# dualstepper.net
KiCad netlist of a schematic drawn in EAGLE
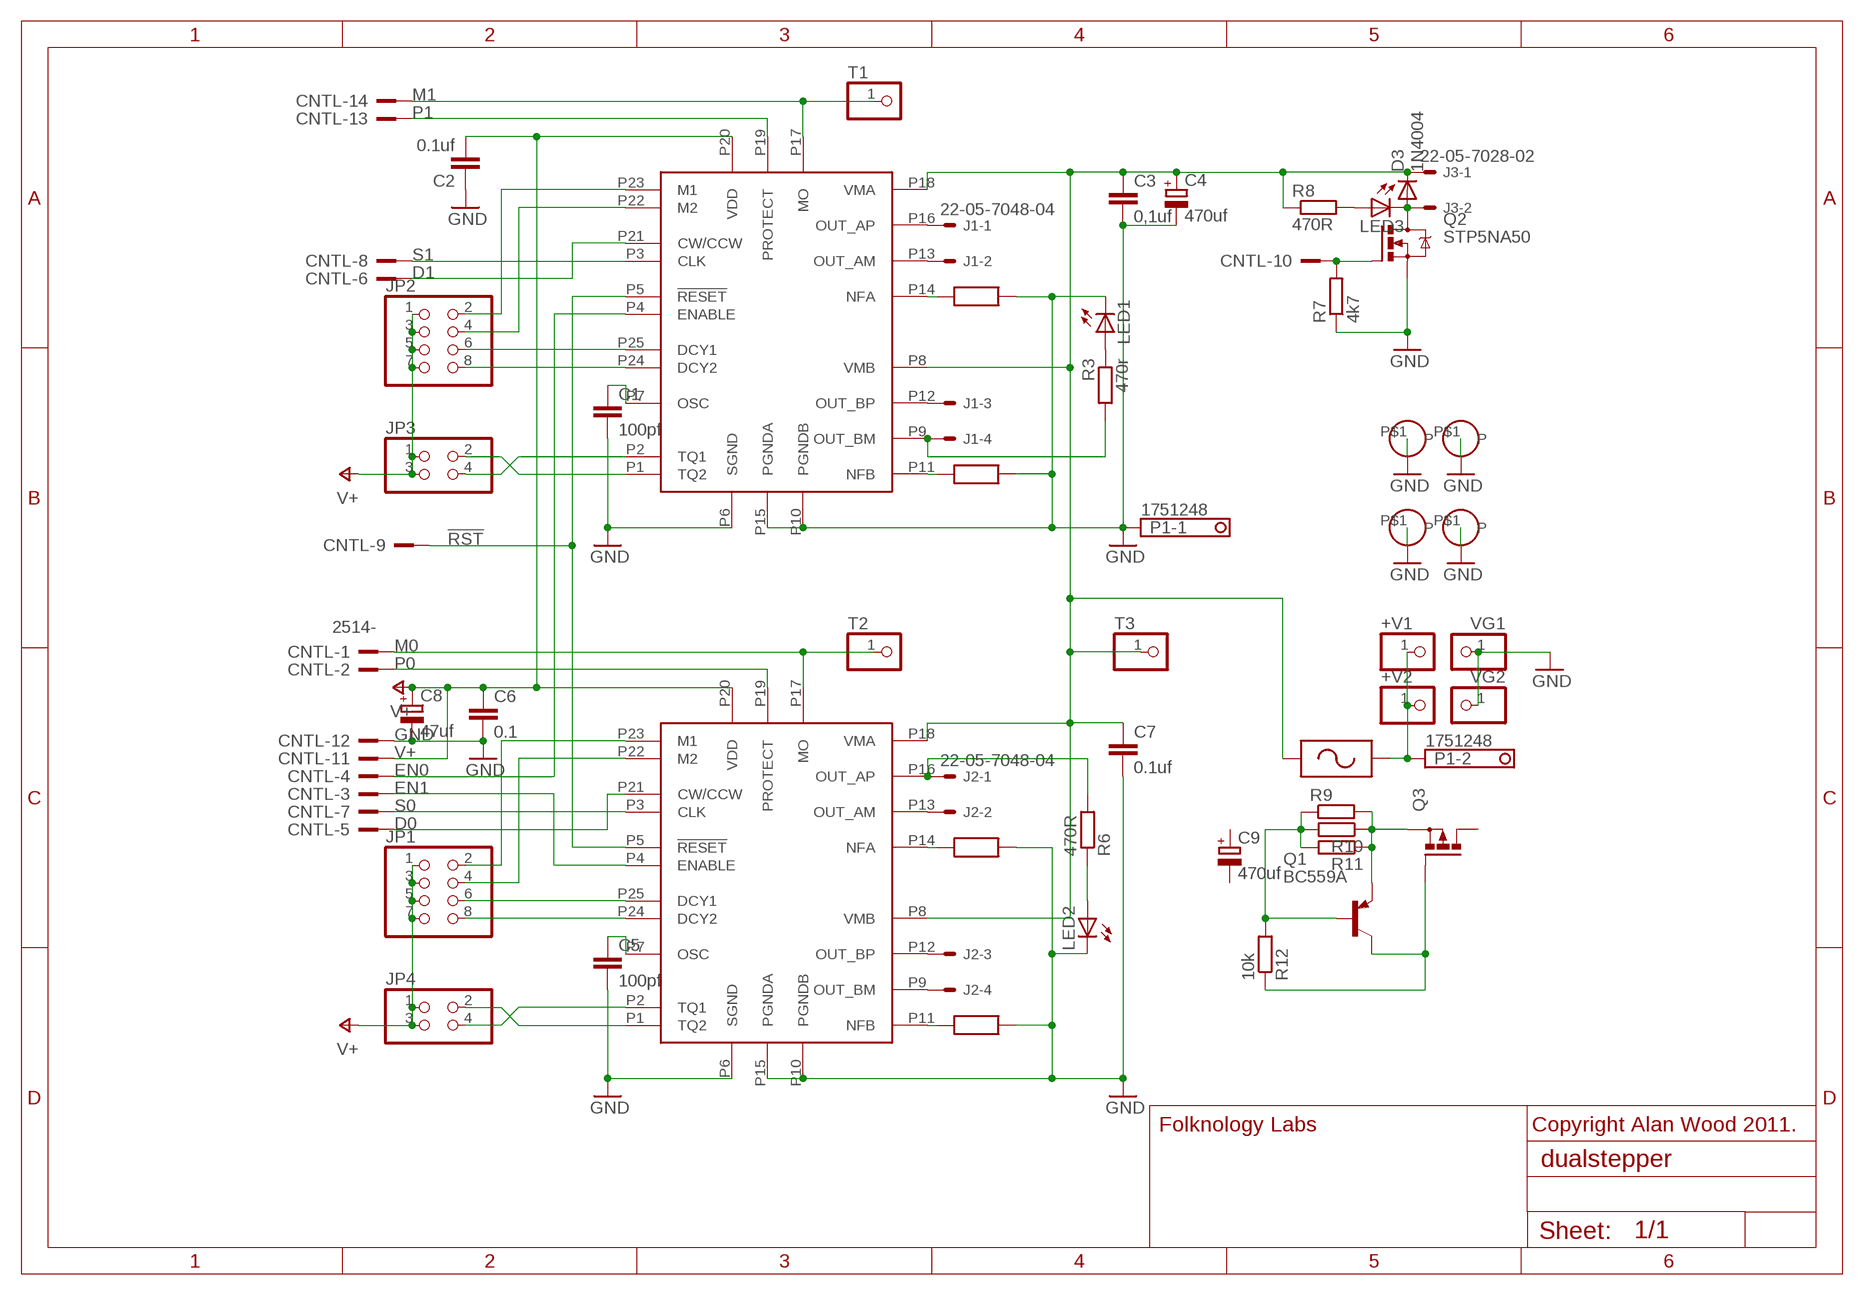
[diagram p0: schematic, sheet 1]

(export (version "E")
  (design (tool "Eeschema 10.0.6"))
  (components
    (comp (ref "+V1")
      (value "PINHD-1X1")
      (footprint "eagle-import:1X01")
      (fields (field (name "MF") "MOLEX") (field (name "MPN") "90120-0761"))
      (libsource (lib "eagle-import") (part "PINHD-1X1"))
    )
    (comp (ref "+V2")
      (value "PINHD-1X1")
      (footprint "eagle-import:1X01")
      (fields (field (name "MF") "MOLEX") (field (name "MPN") "90120-0761"))
      (libsource (lib "eagle-import") (part "PINHD-1X1"))
    )
    (comp (ref "C1")
      (value "100pf")
      (footprint "eagle-import:C025-024X044")
      (fields (field (name "MF") "AVX") (field (name "MPN") "SR151A101JAR"))
      (libsource (lib "eagle-import") (part "C-EU025-024X044"))
    )
    (comp (ref "C2")
      (value "0.1uf")
      (footprint "eagle-import:C025-024X044")
      (fields (field (name "MF") "VISHAY") (field (name "MPN") "K104K15X7RF53L2"))
      (libsource (lib "eagle-import") (part "C-EU025-024X044"))
    )
    (comp (ref "C3")
      (value "0,1uf")
      (footprint "eagle-import:C025-024X044")
      (fields (field (name "MF") "VISHAY") (field (name "MPN") "K104K15X7RF53L2"))
      (libsource (lib "eagle-import") (part "C-EU025-024X044"))
    )
    (comp (ref "C4")
      (value "470uf")
      (footprint "eagle-import:E22-9")
      (fields (field (name "MF") "MULTICOMP") (field (name "MPN") "MCTEA471M1EB-1021P"))
      (libsource (lib "eagle-import") (part "CPOL-EUE22-9AXIAL"))
    )
    (comp (ref "C5")
      (value "100pf")
      (footprint "eagle-import:C025-024X044")
      (fields (field (name "MF") "AVX") (field (name "MPN") "SR151A101JAR"))
      (libsource (lib "eagle-import") (part "C-EU025-024X044"))
    )
    (comp (ref "C6")
      (value "0.1")
      (footprint "eagle-import:C025-024X044")
      (fields (field (name "MF") "VISHAY") (field (name "MPN") "K104K15X7RF53L2"))
      (libsource (lib "eagle-import") (part "C-EU025-024X044"))
    )
    (comp (ref "C7")
      (value "0.1uf")
      (footprint "eagle-import:C025-024X044")
      (fields (field (name "MF") "VISHAY") (field (name "MPN") "K104K15X7RF53L2"))
      (libsource (lib "eagle-import") (part "C-EU025-024X044"))
    )
    (comp (ref "C8")
      (value "47uf")
      (footprint "eagle-import:E1,8-4")
      (fields (field (name "MF") "RUBYCON") (field (name "MPN") "16YXF47MEFC5X11"))
      (libsource (lib "eagle-import") (part "CPOL-EUE1.8-4"))
    )
    (comp (ref "C9")
      (value "470uf")
      (footprint "eagle-import:E3,5-8")
      (fields (field (name "MF") "MULTICOMP") (field (name "MPN") "MCTEA471M1EB-1021P"))
      (libsource (lib "eagle-import") (part "CPOL-EUE3.5-8"))
    )
    (comp (ref "CNTL")
      (value "2514-")
      (footprint "eagle-import:PAK100_2500-14")
      (fields
        (field (name "MF") "HARTING")
        (field (name "MPN") "09 18 510 7323")
        (field (name "OC_FARNELL") "1096980")
      )
      (libsource (lib "eagle-import") (part "2514-"))
    )
    (comp (ref "D3")
      (value "1N4004")
      (footprint "eagle-import:D-7.5")
      (fields (field (name "MF") "ON SEMICONDUCTOR") (field (name "MPN") "1N4004RL"))
      (libsource (lib "eagle-import") (part "DIODE-D-7.5"))
    )
    (comp (ref "J1")
      (value "22-05-7048-04")
      (footprint "eagle-import:7395-04")
      (fields
        (field (name "MF") "MOLEX")
        (field (name "MPN") "22-05-7048")
        (field (name "OC_FARNELL") "9731628")
      )
      (libsource (lib "eagle-import") (part "22-?-0405-7048"))
    )
    (comp (ref "J2")
      (value "22-05-7048-04")
      (footprint "eagle-import:7395-04")
      (fields
        (field (name "MF") "MOLEX")
        (field (name "MPN") "22-05-7048")
        (field (name "OC_FARNELL") "9731628")
      )
      (libsource (lib "eagle-import") (part "22-?-0405-7048"))
    )
    (comp (ref "J3")
      (value "22-05-7028-02")
      (footprint "eagle-import:7395-02")
      (fields
        (field (name "MF") "MOLEX")
        (field (name "MPN") "22-05-7028")
        (field (name "OC_FARNELL") "9731601")
      )
      (libsource (lib "eagle-import") (part "22-?-0205-7028"))
    )
    (comp (ref "JP1")
      (value "PINHD-2X4")
      (footprint "eagle-import:2X04")
      (fields (field (name "MF") "HARWIN") (field (name "MPN") "M20-9980446"))
      (libsource (lib "eagle-import") (part "PINHD-2X4"))
    )
    (comp (ref "JP2")
      (value "PINHD-2X4")
      (footprint "eagle-import:2X04")
      (fields (field (name "MF") "HARWIN") (field (name "MPN") "M20-9980446"))
      (libsource (lib "eagle-import") (part "PINHD-2X4"))
    )
    (comp (ref "JP3")
      (value "PINHD-2X2")
      (footprint "eagle-import:2X02")
      (fields (field (name "MF") "SAMTEC") (field (name "MPN") "TSW-101-07-T-D"))
      (libsource (lib "eagle-import") (part "PINHD-2X2"))
    )
    (comp (ref "JP4")
      (value "PINHD-2X2")
      (footprint "eagle-import:2X02")
      (fields (field (name "MF") "SAMTEC") (field (name "MPN") "TSW-101-07-T-D"))
      (libsource (lib "eagle-import") (part "PINHD-2X2"))
    )
    (comp (ref "LED1")
      (value "LED3MM")
      (footprint "eagle-import:LED3MM")
      (fields (field (name "MF") "KINGBRIGHT") (field (name "MPN") "L-93WEYW"))
      (libsource (lib "eagle-import") (part "LED3MM"))
    )
    (comp (ref "LED2")
      (value "LED3MM")
      (footprint "eagle-import:LED3MM")
      (fields (field (name "MF") "KINGBRIGHT") (field (name "MPN") "L-93WEYW"))
      (libsource (lib "eagle-import") (part "LED3MM"))
    )
    (comp (ref "LED3")
      (value "LED3MM")
      (footprint "eagle-import:LED3MM")
      (fields (field (name "MF") "KINGBRIGHT") (field (name "MPN") "L-93WEYW"))
      (libsource (lib "eagle-import") (part "LED3MM"))
    )
    (comp (ref "P1")
      (value "1751248")
      (footprint "eagle-import:1751248")
      (fields
        (field (name "MF") "CAMDEN")
        (field (name "MPN") "CTB3051/2")
        (field (name "OC_FARNELL") "3882615")
      )
      (libsource (lib "eagle-import") (part "1751248"))
    )
    (comp (ref "Q1")
      (value "BC559A")
      (footprint "eagle-import:TO92-EBC")
      (libsource (lib "eagle-import") (part "BC559A"))
    )
    (comp (ref "Q2")
      (value "STP5NA50")
      (footprint "eagle-import:TO220BV")
      (fields (field (name "MF") "STMICROELECTRONICS") (field (name "MPN") "STP55NF06L."))
      (libsource (lib "eagle-import") (part "STP5NA50"))
    )
    (comp (ref "Q3")
      (value "PMOSFET_PTO220BV")
      (footprint "eagle-import:TO220BV")
      (libsource (lib "eagle-import") (part "PMOSFET_PTO220BV"))
    )
    (comp (ref "R1")
      (value "R22")
      (footprint "eagle-import:R20")
      (fields (field (name "MF") "WELWYN") (field (name "MPN") "WP4S-R22JA2"))
      (libsource (lib "eagle-import") (part "3W-WIREWOUND-RESISTOR"))
    )
    (comp (ref "R2")
      (value "R22")
      (footprint "eagle-import:R20")
      (fields (field (name "MF") "WELWYN") (field (name "MPN") "WP4S-R22JA2"))
      (libsource (lib "eagle-import") (part "3W-WIREWOUND-RESISTOR"))
    )
    (comp (ref "R3")
      (value "470r")
      (footprint "eagle-import:0204_7")
      (fields (field (name "MF") "WELWYN") (field (name "MPN") "MFR4 470R 1%"))
      (libsource (lib "eagle-import") (part "R-EU_0204/7"))
    )
    (comp (ref "R4")
      (value "R22")
      (footprint "eagle-import:R20")
      (fields (field (name "MF") "WELWYN") (field (name "MPN") "WP4S-R22JA2"))
      (libsource (lib "eagle-import") (part "3W-WIREWOUND-RESISTOR"))
    )
    (comp (ref "R5")
      (value "R22")
      (footprint "eagle-import:R20")
      (fields (field (name "MF") "WELWYN") (field (name "MPN") "WP4S-R22JA2"))
      (libsource (lib "eagle-import") (part "3W-WIREWOUND-RESISTOR"))
    )
    (comp (ref "R6")
      (value "470R")
      (footprint "eagle-import:0204_7")
      (fields (field (name "MF") "WELWYN") (field (name "MPN") "MFR4 470R 1%"))
      (libsource (lib "eagle-import") (part "R-EU_0204/7"))
    )
    (comp (ref "R7")
      (value "4k7")
      (footprint "eagle-import:0204_7")
      (fields (field (name "MF") "WELWYN") (field (name "MPN") "MFR4 10K 1%"))
      (libsource (lib "eagle-import") (part "resistor_R-EU_0204/7"))
    )
    (comp (ref "R8")
      (value "470R")
      (footprint "eagle-import:0204_7")
      (fields (field (name "MF") "WELWYN") (field (name "MPN") "MFR4 470R 1%"))
      (libsource (lib "eagle-import") (part "resistor_R-EU_0204/7"))
    )
    (comp (ref "R9")
      (value "R-EU_0411/3V")
      (footprint "eagle-import:0411V")
      (libsource (lib "eagle-import") (part "resistor_R-EU_0411/3V"))
    )
    (comp (ref "R10")
      (value "R-EU_0411/3V")
      (footprint "eagle-import:0411V")
      (libsource (lib "eagle-import") (part "resistor_R-EU_0411/3V"))
    )
    (comp (ref "R11")
      (value "R-EU_0411/3V")
      (footprint "eagle-import:0411V")
      (libsource (lib "eagle-import") (part "resistor_R-EU_0411/3V"))
    )
    (comp (ref "R12")
      (value "10k")
      (footprint "eagle-import:0204_7")
      (fields (field (name "MF") "WELWYN") (field (name "MPN") "MFR4 470R 1%"))
      (libsource (lib "eagle-import") (part "R-EU_0204/7"))
    )
    (comp (ref "T1")
      (value "PINHD-1X1")
      (footprint "eagle-import:1X01")
      (fields (field (name "MF") "MOLEX") (field (name "MPN") "90120-0761"))
      (libsource (lib "eagle-import") (part "PINHD-1X1"))
    )
    (comp (ref "T2")
      (value "PINHD-1X1")
      (footprint "eagle-import:1X01")
      (fields (field (name "MF") "MOLEX") (field (name "MPN") "90120-0761"))
      (libsource (lib "eagle-import") (part "PINHD-1X1"))
    )
    (comp (ref "T3")
      (value "PINHD-1X1")
      (footprint "eagle-import:1X01")
      (fields (field (name "MF") "MOLEX") (field (name "MPN") "90120-0761"))
      (libsource (lib "eagle-import") (part "PINHD-1X1"))
    )
    (comp (ref "U$1")
      (value "TB6560AHQ")
      (footprint "eagle-import:HZIP25-P-1.27")
      (libsource (lib "eagle-import") (part "TB6560AHQ"))
    )
    (comp (ref "U$2")
      (value "TB6560AHQ")
      (footprint "eagle-import:HZIP25-P-1.27")
      (libsource (lib "eagle-import") (part "TB6560AHQ"))
    )
    (comp (ref "U$3")
      (value "HOLE")
      (footprint "eagle-import:HOLE")
      (libsource (lib "eagle-import") (part "HOLE"))
    )
    (comp (ref "U$4")
      (value "HOLE")
      (footprint "eagle-import:HOLE")
      (libsource (lib "eagle-import") (part "HOLE"))
    )
    (comp (ref "U$5")
      (value "HOLE")
      (footprint "eagle-import:HOLE")
      (libsource (lib "eagle-import") (part "HOLE"))
    )
    (comp (ref "U$6")
      (value "HOLE")
      (footprint "eagle-import:HOLE")
      (libsource (lib "eagle-import") (part "HOLE"))
    )
    (comp (ref "U$7")
      (value "RXEFXXX-RAYCHEM-POLYSWITCH10.2")
      (footprint "eagle-import:2_10.2")
      (fields (field (name "MF") "TE CONNECTIVITY / RAYCHEM") (field (name "MPN") "AGRF1000"))
      (libsource (lib "eagle-import") (part "RXEFXXX-RAYCHEM-POLYSWITCH10.2"))
    )
    (comp (ref "VG1")
      (value "PINHD-1X1")
      (footprint "eagle-import:1X01")
      (fields (field (name "MF") "MOLEX") (field (name "MPN") "90120-0761"))
      (libsource (lib "eagle-import") (part "PINHD-1X1"))
    )
    (comp (ref "VG2")
      (value "PINHD-1X1")
      (footprint "eagle-import:1X01")
      (fields (field (name "MF") "MOLEX") (field (name "MPN") "90120-0761"))
      (libsource (lib "eagle-import") (part "PINHD-1X1"))
    )
  )
  (nets
    (net (code "1") (name "/D0") (class "Default")
      (node (ref "CNTL") (pin "5") (pinfunction "KL_5") (pintype "passive"))
      (node (ref "U$1") (pin "P21") (pinfunction "CW/CCW_P21") (pintype "input"))
    )
    (net (code "2") (name "/D1") (class "Default")
      (node (ref "CNTL") (pin "6") (pinfunction "KL_6") (pintype "passive"))
      (node (ref "U$2") (pin "P21") (pinfunction "CW/CCW_P21") (pintype "input"))
    )
    (net (code "3") (name "/EN0") (class "Default")
      (node (ref "CNTL") (pin "4") (pinfunction "KL_4") (pintype "passive"))
      (node (ref "U$2") (pin "P4") (pinfunction "ENABLE_P4") (pintype "input"))
    )
    (net (code "4") (name "/EN1") (class "Default")
      (node (ref "CNTL") (pin "3") (pinfunction "KL_3") (pintype "passive"))
      (node (ref "U$1") (pin "P4") (pinfunction "ENABLE_P4") (pintype "input"))
    )
    (net (code "5") (name "/M0") (class "Default")
      (node (ref "CNTL") (pin "1") (pinfunction "KL_1") (pintype "passive"))
      (node (ref "T2") (pin "1") (pinfunction "1_1") (pintype "passive"))
      (node (ref "U$1") (pin "P17") (pinfunction "MO_P17") (pintype "output"))
    )
    (net (code "6") (name "/M1") (class "Default")
      (node (ref "CNTL") (pin "14") (pinfunction "KL_14") (pintype "passive"))
      (node (ref "T1") (pin "1") (pinfunction "1_1") (pintype "passive"))
      (node (ref "U$2") (pin "P17") (pinfunction "MO_P17") (pintype "output"))
    )
    (net (code "7") (name "/P0") (class "Default")
      (node (ref "CNTL") (pin "2") (pinfunction "KL_2") (pintype "passive"))
      (node (ref "U$1") (pin "P19") (pinfunction "PROTECT_P19") (pintype "output"))
    )
    (net (code "8") (name "/P1") (class "Default")
      (node (ref "CNTL") (pin "13") (pinfunction "KL_13") (pintype "passive"))
      (node (ref "U$2") (pin "P19") (pinfunction "PROTECT_P19") (pintype "output"))
    )
    (net (code "9") (name "/S0") (class "Default")
      (node (ref "CNTL") (pin "7") (pinfunction "KL_7") (pintype "passive"))
      (node (ref "U$1") (pin "P3") (pinfunction "CLK_P3") (pintype "input"))
    )
    (net (code "10") (name "/S1") (class "Default")
      (node (ref "CNTL") (pin "8") (pinfunction "KL_8") (pintype "passive"))
      (node (ref "U$2") (pin "P3") (pinfunction "CLK_P3") (pintype "input"))
    )
    (net (code "11") (name "/~{RST}") (class "Default")
      (node (ref "CNTL") (pin "9") (pinfunction "KL_9") (pintype "passive"))
      (node (ref "U$1") (pin "P5") (pinfunction "~{RESET}_P5") (pintype "bidirectional"))
      (node (ref "U$2") (pin "P5") (pinfunction "~{RESET}_P5") (pintype "bidirectional"))
    )
    (net (code "12") (name "GND") (class "Default")
      (node (ref "C1") (pin "2") (pinfunction "2_2") (pintype "passive"))
      (node (ref "C2") (pin "1") (pinfunction "1_1") (pintype "passive"))
      (node (ref "C3") (pin "2") (pinfunction "2_2") (pintype "passive"))
      (node (ref "C4") (pin "-") (pinfunction "-_-") (pintype "passive"))
      (node (ref "C5") (pin "2") (pinfunction "2_2") (pintype "passive"))
      (node (ref "C6") (pin "2") (pinfunction "2_2") (pintype "passive"))
      (node (ref "C7") (pin "2") (pinfunction "2_2") (pintype "passive"))
      (node (ref "C8") (pin "-") (pinfunction "-_-") (pintype "passive"))
      (node (ref "CNTL") (pin "12") (pinfunction "KL_12") (pintype "passive"))
      (node (ref "LED1") (pin "K") (pinfunction "C_K") (pintype "passive"))
      (node (ref "LED2") (pin "K") (pinfunction "C_K") (pintype "passive"))
      (node (ref "P1") (pin "1") (pinfunction "K_1") (pintype "passive"))
      (node (ref "Q2") (pin "S") (pinfunction "S_S") (pintype "passive"))
      (node (ref "R1") (pin "P$2") (pinfunction "2_P$2") (pintype "passive"))
      (node (ref "R2") (pin "P$2") (pinfunction "2_P$2") (pintype "passive"))
      (node (ref "R4") (pin "P$2") (pinfunction "2_P$2") (pintype "passive"))
      (node (ref "R5") (pin "P$2") (pinfunction "2_P$2") (pintype "passive"))
      (node (ref "R7") (pin "1") (pinfunction "1_1") (pintype "passive"))
      (node (ref "U$1") (pin "P10") (pinfunction "PGNDB_P10") (pintype "bidirectional"))
      (node (ref "U$1") (pin "P15") (pinfunction "PGNDA_P15") (pintype "bidirectional"))
      (node (ref "U$1") (pin "P6") (pinfunction "SGND_P6") (pintype "power_in"))
      (node (ref "U$2") (pin "P10") (pinfunction "PGNDB_P10") (pintype "bidirectional"))
      (node (ref "U$2") (pin "P15") (pinfunction "PGNDA_P15") (pintype "bidirectional"))
      (node (ref "U$2") (pin "P6") (pinfunction "SGND_P6") (pintype "power_in"))
      (node (ref "U$3") (pin "P$1") (pinfunction "P_P$1") (pintype "bidirectional"))
      (node (ref "U$4") (pin "P$1") (pinfunction "P_P$1") (pintype "bidirectional"))
      (node (ref "U$5") (pin "P$1") (pinfunction "P_P$1") (pintype "bidirectional"))
      (node (ref "U$6") (pin "P$1") (pinfunction "P_P$1") (pintype "bidirectional"))
      (node (ref "VG1") (pin "1") (pinfunction "1_1") (pintype "passive"))
      (node (ref "VG2") (pin "1") (pinfunction "1_1") (pintype "passive"))
    )
    (net (code "13") (name "Net-(CNTLB-KL)") (class "Default")
      (node (ref "CNTL") (pin "10") (pinfunction "KL_10") (pintype "passive"))
      (node (ref "Q2") (pin "G") (pinfunction "G_G") (pintype "passive"))
      (node (ref "R7") (pin "2") (pinfunction "2_2") (pintype "passive"))
    )
    (net (code "14") (name "Net-(J1A-S)") (class "Default")
      (node (ref "J1") (pin "1") (pinfunction "S_1") (pintype "passive"))
      (node (ref "U$2") (pin "P16") (pinfunction "OUT_AP_P16") (pintype "output"))
    )
    (net (code "15") (name "Net-(J1B-S)") (class "Default")
      (node (ref "J1") (pin "2") (pinfunction "S_2") (pintype "passive"))
      (node (ref "U$2") (pin "P13") (pinfunction "OUT_AM_P13") (pintype "output"))
    )
    (net (code "16") (name "Net-(J1C-S)") (class "Default")
      (node (ref "J1") (pin "3") (pinfunction "S_3") (pintype "passive"))
      (node (ref "U$2") (pin "P12") (pinfunction "OUT_BP_P12") (pintype "output"))
    )
    (net (code "17") (name "Net-(J1D-S)") (class "Default")
      (node (ref "J1") (pin "4") (pinfunction "S_4") (pintype "passive"))
      (node (ref "R3") (pin "2") (pinfunction "2_2") (pintype "passive"))
      (node (ref "U$2") (pin "P9") (pinfunction "OUT_BM_P9") (pintype "output"))
    )
    (net (code "18") (name "Net-(J2A-S)") (class "Default")
      (node (ref "J2") (pin "1") (pinfunction "S_1") (pintype "passive"))
      (node (ref "R6") (pin "2") (pinfunction "2_2") (pintype "passive"))
      (node (ref "U$1") (pin "P16") (pinfunction "OUT_AP_P16") (pintype "output"))
    )
    (net (code "19") (name "Net-(J2B-S)") (class "Default")
      (node (ref "J2") (pin "2") (pinfunction "S_2") (pintype "passive"))
      (node (ref "U$1") (pin "P13") (pinfunction "OUT_AM_P13") (pintype "output"))
    )
    (net (code "20") (name "Net-(J2C-S)") (class "Default")
      (node (ref "J2") (pin "3") (pinfunction "S_3") (pintype "passive"))
      (node (ref "U$1") (pin "P12") (pinfunction "OUT_BP_P12") (pintype "output"))
    )
    (net (code "21") (name "Net-(J2D-S)") (class "Default")
      (node (ref "J2") (pin "4") (pinfunction "S_4") (pintype "passive"))
      (node (ref "U$1") (pin "P9") (pinfunction "OUT_BM_P9") (pintype "output"))
    )
    (net (code "22") (name "Net-(J3A-S)") (class "Default")
      (node (ref "C3") (pin "1") (pinfunction "1_1") (pintype "passive"))
      (node (ref "C4") (pin "+") (pinfunction "+_+") (pintype "passive"))
      (node (ref "C7") (pin "1") (pinfunction "1_1") (pintype "passive"))
      (node (ref "D3") (pin "C") (pinfunction "C_C") (pintype "passive"))
      (node (ref "J3") (pin "1") (pinfunction "S_1") (pintype "passive"))
      (node (ref "R8") (pin "1") (pinfunction "1_1") (pintype "passive"))
      (node (ref "T3") (pin "1") (pinfunction "1_1") (pintype "passive"))
      (node (ref "U$1") (pin "P18") (pinfunction "VMA_P18") (pintype "power_in"))
      (node (ref "U$1") (pin "P8") (pinfunction "VMB_P8") (pintype "power_in"))
      (node (ref "U$2") (pin "P18") (pinfunction "VMA_P18") (pintype "power_in"))
      (node (ref "U$2") (pin "P8") (pinfunction "VMB_P8") (pintype "power_in"))
      (node (ref "U$7") (pin "P$1") (pinfunction "P$1_P$1") (pintype "passive"))
    )
    (net (code "23") (name "Net-(J3B-S)") (class "Default")
      (node (ref "D3") (pin "A") (pinfunction "A_A") (pintype "passive"))
      (node (ref "J3") (pin "2") (pinfunction "S_2") (pintype "passive"))
      (node (ref "LED3") (pin "K") (pinfunction "C_K") (pintype "passive"))
      (node (ref "Q2") (pin "D") (pinfunction "D_D") (pintype "passive"))
    )
    (net (code "24") (name "Net-(LED1-PadA)") (class "Default")
      (node (ref "LED1") (pin "A") (pinfunction "A_A") (pintype "passive"))
      (node (ref "R3") (pin "1") (pinfunction "1_1") (pintype "passive"))
    )
    (net (code "25") (name "Net-(LED2-PadA)") (class "Default")
      (node (ref "LED2") (pin "A") (pinfunction "A_A") (pintype "passive"))
      (node (ref "R6") (pin "1") (pinfunction "1_1") (pintype "passive"))
    )
    (net (code "26") (name "Net-(LED3-PadA)") (class "Default")
      (node (ref "LED3") (pin "A") (pinfunction "A_A") (pintype "passive"))
      (node (ref "R8") (pin "2") (pinfunction "2_2") (pintype "passive"))
    )
    (net (code "27") (name "Net-(P1B-K)") (class "Default")
      (node (ref "+V1") (pin "1") (pinfunction "1_1") (pintype "passive"))
      (node (ref "+V2") (pin "1") (pinfunction "1_1") (pintype "passive"))
      (node (ref "P1") (pin "2") (pinfunction "K_2") (pintype "passive"))
      (node (ref "U$7") (pin "P$2") (pinfunction "P$2_P$2") (pintype "passive"))
    )
    (net (code "28") (name "Net-(Q1-PadB)") (class "Default")
      (node (ref "Q1") (pin "B") (pinfunction "B_B") (pintype "passive"))
      (node (ref "R10") (pin "2") (pinfunction "2_2") (pintype "passive"))
      (node (ref "R11") (pin "2") (pinfunction "2_2") (pintype "passive"))
      (node (ref "R12") (pin "2") (pinfunction "2_2") (pintype "passive"))
      (node (ref "R9") (pin "1") (pinfunction "1_1") (pintype "passive"))
    )
    (net (code "29") (name "Net-(Q1-PadC)") (class "Default")
      (node (ref "Q1") (pin "C") (pinfunction "C_C") (pintype "passive"))
      (node (ref "Q3") (pin "G") (pinfunction "G_G") (pintype "passive"))
      (node (ref "R12") (pin "1") (pinfunction "1_1") (pintype "passive"))
    )
    (net (code "30") (name "Net-(Q1-PadE)") (class "Default")
      (node (ref "Q1") (pin "E") (pinfunction "E_E") (pintype "passive"))
      (node (ref "Q3") (pin "S") (pinfunction "S_S") (pintype "passive"))
      (node (ref "R10") (pin "1") (pinfunction "1_1") (pintype "passive"))
      (node (ref "R11") (pin "1") (pinfunction "1_1") (pintype "passive"))
      (node (ref "R9") (pin "2") (pinfunction "2_2") (pintype "passive"))
    )
    (net (code "31") (name "Net-(R1-1)") (class "Default")
      (node (ref "R1") (pin "P$1") (pinfunction "1_P$1") (pintype "passive"))
      (node (ref "U$2") (pin "P14") (pinfunction "NFA_P14") (pintype "output"))
    )
    (net (code "32") (name "Net-(R2-1)") (class "Default")
      (node (ref "R2") (pin "P$1") (pinfunction "1_P$1") (pintype "passive"))
      (node (ref "U$2") (pin "P11") (pinfunction "NFB_P11") (pintype "output"))
    )
    (net (code "33") (name "Net-(R4-1)") (class "Default")
      (node (ref "R4") (pin "P$1") (pinfunction "1_P$1") (pintype "passive"))
      (node (ref "U$1") (pin "P14") (pinfunction "NFA_P14") (pintype "output"))
    )
    (net (code "34") (name "Net-(R5-1)") (class "Default")
      (node (ref "R5") (pin "P$1") (pinfunction "1_P$1") (pintype "passive"))
      (node (ref "U$1") (pin "P11") (pinfunction "NFB_P11") (pintype "output"))
    )
    (net (code "35") (name "Net-(U$1-DCY1)") (class "Default")
      (node (ref "JP1") (pin "6") (pinfunction "6_6") (pintype "passive"))
      (node (ref "U$1") (pin "P25") (pinfunction "DCY1_P25") (pintype "input"))
    )
    (net (code "36") (name "Net-(U$1-DCY2)") (class "Default")
      (node (ref "JP1") (pin "8") (pinfunction "8_8") (pintype "passive"))
      (node (ref "U$1") (pin "P24") (pinfunction "DCY2_P24") (pintype "input"))
    )
    (net (code "37") (name "Net-(U$1-M1)") (class "Default")
      (node (ref "JP1") (pin "2") (pinfunction "2_2") (pintype "passive"))
      (node (ref "U$1") (pin "P23") (pinfunction "M1_P23") (pintype "input"))
    )
    (net (code "38") (name "Net-(U$1-M2)") (class "Default")
      (node (ref "JP1") (pin "4") (pinfunction "4_4") (pintype "passive"))
      (node (ref "U$1") (pin "P22") (pinfunction "M2_P22") (pintype "bidirectional"))
    )
    (net (code "39") (name "Net-(U$1-OSC)") (class "Default")
      (node (ref "C5") (pin "1") (pinfunction "1_1") (pintype "passive"))
      (node (ref "U$1") (pin "P7") (pinfunction "OSC_P7") (pintype "passive"))
    )
    (net (code "40") (name "Net-(U$1-TQ1)") (class "Default")
      (node (ref "JP4") (pin "4") (pinfunction "4_4") (pintype "passive"))
      (node (ref "U$1") (pin "P2") (pinfunction "TQ1_P2") (pintype "input"))
    )
    (net (code "41") (name "Net-(U$1-TQ2)") (class "Default")
      (node (ref "JP4") (pin "2") (pinfunction "2_2") (pintype "passive"))
      (node (ref "U$1") (pin "P1") (pinfunction "TQ2_P1") (pintype "input"))
    )
    (net (code "42") (name "Net-(U$2-DCY1)") (class "Default")
      (node (ref "JP2") (pin "6") (pinfunction "6_6") (pintype "passive"))
      (node (ref "U$2") (pin "P25") (pinfunction "DCY1_P25") (pintype "input"))
    )
    (net (code "43") (name "Net-(U$2-DCY2)") (class "Default")
      (node (ref "JP2") (pin "8") (pinfunction "8_8") (pintype "passive"))
      (node (ref "U$2") (pin "P24") (pinfunction "DCY2_P24") (pintype "input"))
    )
    (net (code "44") (name "Net-(U$2-M1)") (class "Default")
      (node (ref "JP2") (pin "2") (pinfunction "2_2") (pintype "passive"))
      (node (ref "U$2") (pin "P23") (pinfunction "M1_P23") (pintype "input"))
    )
    (net (code "45") (name "Net-(U$2-M2)") (class "Default")
      (node (ref "JP2") (pin "4") (pinfunction "4_4") (pintype "passive"))
      (node (ref "U$2") (pin "P22") (pinfunction "M2_P22") (pintype "bidirectional"))
    )
    (net (code "46") (name "Net-(U$2-OSC)") (class "Default")
      (node (ref "C1") (pin "1") (pinfunction "1_1") (pintype "passive"))
      (node (ref "U$2") (pin "P7") (pinfunction "OSC_P7") (pintype "passive"))
    )
    (net (code "47") (name "Net-(U$2-TQ1)") (class "Default")
      (node (ref "JP3") (pin "4") (pinfunction "4_4") (pintype "passive"))
      (node (ref "U$2") (pin "P2") (pinfunction "TQ1_P2") (pintype "input"))
    )
    (net (code "48") (name "Net-(U$2-TQ2)") (class "Default")
      (node (ref "JP3") (pin "2") (pinfunction "2_2") (pintype "passive"))
      (node (ref "U$2") (pin "P1") (pinfunction "TQ2_P1") (pintype "input"))
    )
    (net (code "49") (name "V+") (class "Default")
      (node (ref "C2") (pin "2") (pinfunction "2_2") (pintype "passive"))
      (node (ref "C6") (pin "1") (pinfunction "1_1") (pintype "passive"))
      (node (ref "C8") (pin "+") (pinfunction "+_+") (pintype "passive"))
      (node (ref "CNTL") (pin "11") (pinfunction "KL_11") (pintype "passive"))
      (node (ref "JP1") (pin "1") (pinfunction "1_1") (pintype "passive"))
      (node (ref "JP1") (pin "3") (pinfunction "3_3") (pintype "passive"))
      (node (ref "JP1") (pin "5") (pinfunction "5_5") (pintype "passive"))
      (node (ref "JP1") (pin "7") (pinfunction "7_7") (pintype "passive"))
      (node (ref "JP2") (pin "1") (pinfunction "1_1") (pintype "passive"))
      (node (ref "JP2") (pin "3") (pinfunction "3_3") (pintype "passive"))
      (node (ref "JP2") (pin "5") (pinfunction "5_5") (pintype "passive"))
      (node (ref "JP2") (pin "7") (pinfunction "7_7") (pintype "passive"))
      (node (ref "JP3") (pin "1") (pinfunction "1_1") (pintype "passive"))
      (node (ref "JP3") (pin "3") (pinfunction "3_3") (pintype "passive"))
      (node (ref "JP4") (pin "1") (pinfunction "1_1") (pintype "passive"))
      (node (ref "JP4") (pin "3") (pinfunction "3_3") (pintype "passive"))
      (node (ref "U$1") (pin "P20") (pinfunction "VDD_P20") (pintype "power_in"))
      (node (ref "U$2") (pin "P20") (pinfunction "VDD_P20") (pintype "power_in"))
    )
    (net (code "50") (name "unconnected-(C9-Pad+)") (class "Default")
      (node (ref "C9") (pin "+") (pinfunction "+_+") (pintype "passive"))
    )
    (net (code "51") (name "unconnected-(C9-Pad-)") (class "Default")
      (node (ref "C9") (pin "-") (pinfunction "-_-") (pintype "passive"))
    )
    (net (code "52") (name "unconnected-(Q3-PadD)") (class "Default")
      (node (ref "Q3") (pin "D") (pinfunction "D_D") (pintype "passive"))
    )
  )
)
